# pll_schematic.net
KiCad netlist of a schematic drawn in Altium Designer
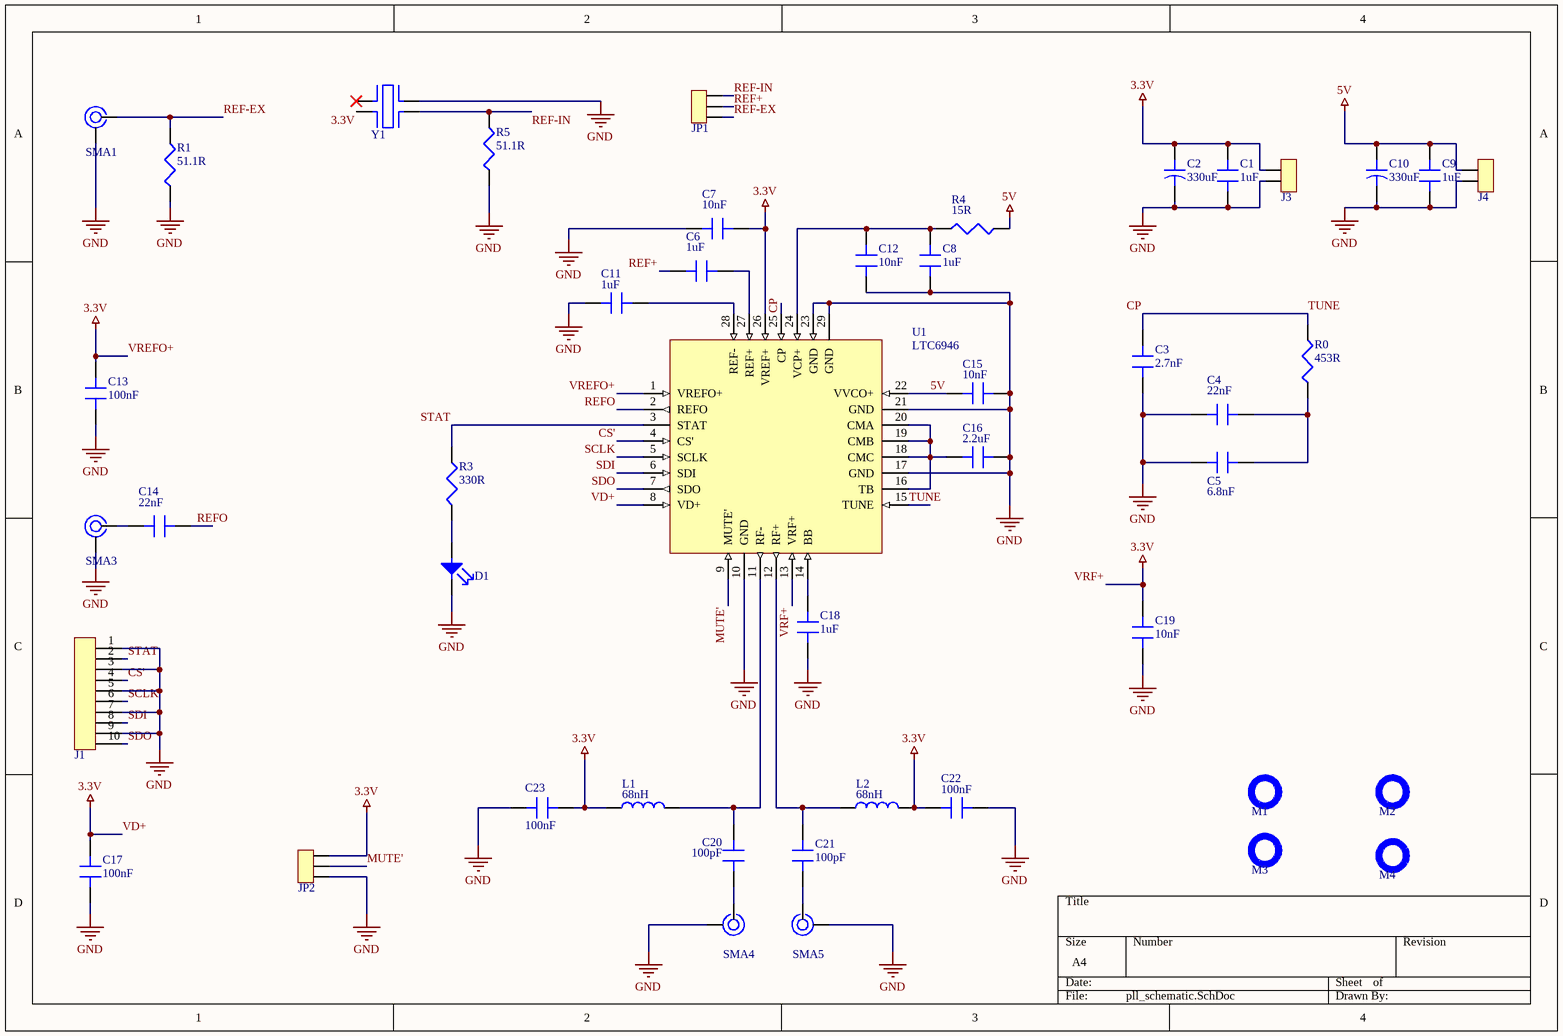
[diagram p0: pll_schematic.SchDoc]

(export (version "E")
  (design (tool "Eeschema 10.0.6"))
  (components
    (comp (ref "C1") (value "1uF") (footprint "C0603") (libsource (lib "pll_schematic_lib") (part "C")))
    (comp (ref "C2") (value "330uF") (footprint "C_TANT_D") (libsource (lib "pll_schematic_lib") (part "CP")))
    (comp (ref "C3") (value "2.7nF") (footprint "C0603") (libsource (lib "pll_schematic_lib") (part "C")))
    (comp (ref "C4") (value "22nF") (footprint "C0603") (libsource (lib "pll_schematic_lib") (part "C")))
    (comp (ref "C5") (value "6.8nF") (footprint "C0603") (libsource (lib "pll_schematic_lib") (part "C")))
    (comp (ref "C6") (value "1uF") (footprint "C0603") (libsource (lib "pll_schematic_lib") (part "C")))
    (comp (ref "C7") (value "10nF") (footprint "C0603") (libsource (lib "pll_schematic_lib") (part "C")))
    (comp (ref "C8") (value "1uF") (footprint "C0603") (libsource (lib "pll_schematic_lib") (part "C")))
    (comp (ref "C9") (value "1uF") (footprint "C0603") (libsource (lib "pll_schematic_lib") (part "C")))
    (comp (ref "C10")
      (value "330uF")
      (footprint "C_TANT_D")
      (libsource (lib "pll_schematic_lib") (part "CP"))
    )
    (comp (ref "C11") (value "1uF") (footprint "C0603") (libsource (lib "pll_schematic_lib") (part "C")))
    (comp (ref "C12") (value "10nF") (footprint "C0603") (libsource (lib "pll_schematic_lib") (part "C")))
    (comp (ref "C13") (value "100nF") (footprint "C0603") (libsource (lib "pll_schematic_lib") (part "C")))
    (comp (ref "C14") (value "22nF") (footprint "C0603") (libsource (lib "pll_schematic_lib") (part "C")))
    (comp (ref "C15") (value "10nF") (footprint "C0603") (libsource (lib "pll_schematic_lib") (part "C")))
    (comp (ref "C16") (value "2.2uF") (footprint "C0805") (libsource (lib "pll_schematic_lib") (part "C")))
    (comp (ref "C17") (value "100nF") (footprint "C0603") (libsource (lib "pll_schematic_lib") (part "C")))
    (comp (ref "C18") (value "1uF") (footprint "C0603") (libsource (lib "pll_schematic_lib") (part "C")))
    (comp (ref "C19") (value "10nF") (footprint "C0603") (libsource (lib "pll_schematic_lib") (part "C")))
    (comp (ref "C20") (value "100pF") (footprint "C0603") (libsource (lib "pll_schematic_lib") (part "C")))
    (comp (ref "C21") (value "100pF") (footprint "C0603") (libsource (lib "pll_schematic_lib") (part "C")))
    (comp (ref "C22") (value "100nF") (footprint "C0603") (libsource (lib "pll_schematic_lib") (part "C")))
    (comp (ref "C23") (value "100nF") (footprint "C0603") (libsource (lib "pll_schematic_lib") (part "C")))
    (comp (ref "D1") (value "-") (footprint "D0805") (libsource (lib "pll_schematic_lib") (part "LED")))
    (comp (ref "J1")
      (value "-")
      (footprint "IDC-2x05")
      (libsource (lib "pll_schematic_lib") (part "Conn_Gene_1x10"))
    )
    (comp (ref "J3")
      (value "-")
      (footprint "JST_XH_1X02")
      (libsource (lib "pll_schematic_lib") (part "Conn_Gene_1x02"))
    )
    (comp (ref "J4")
      (value "-")
      (footprint "JST_XH_1X02")
      (libsource (lib "pll_schematic_lib") (part "Conn_Gene_1x02"))
    )
    (comp (ref "JP1")
      (value "-")
      (footprint "PIN_HEADER_1x03")
      (libsource (lib "pll_schematic_lib") (part "Pin Header 1x03"))
    )
    (comp (ref "JP2")
      (value "-")
      (footprint "PIN_HEADER_1x03")
      (libsource (lib "pll_schematic_lib") (part "Pin Header 1x03"))
    )
    (comp (ref "L1") (value "68nH") (footprint "L0402") (libsource (lib "pll_schematic_lib") (part "L")))
    (comp (ref "L2") (value "68nH") (footprint "L0402") (libsource (lib "pll_schematic_lib") (part "L")))
    (comp (ref "M1")
      (value "MOUNTING_HOLE")
      (footprint "MOUNTING_HOLE_NP_M3")
      (description "Non-Plated")
      (libsource (lib "pll_schematic_lib") (part "MOUNTING_HOLE"))
    )
    (comp (ref "M2")
      (value "MOUNTING_HOLE")
      (footprint "MOUNTING_HOLE_NP_M3")
      (description "Non-Plated")
      (libsource (lib "pll_schematic_lib") (part "MOUNTING_HOLE"))
    )
    (comp (ref "M3")
      (value "MOUNTING_HOLE")
      (footprint "MOUNTING_HOLE_NP_M3")
      (description "Non-Plated")
      (libsource (lib "pll_schematic_lib") (part "MOUNTING_HOLE"))
    )
    (comp (ref "M4")
      (value "MOUNTING_HOLE")
      (footprint "MOUNTING_HOLE_NP_M3")
      (description "Non-Plated")
      (libsource (lib "pll_schematic_lib") (part "MOUNTING_HOLE"))
    )
    (comp (ref "R0") (value "453R") (footprint "R0603") (libsource (lib "pll_schematic_lib") (part "R")))
    (comp (ref "R1") (value "51.1R") (footprint "R0603") (libsource (lib "pll_schematic_lib") (part "R")))
    (comp (ref "R3") (value "330R") (footprint "R0603") (libsource (lib "pll_schematic_lib") (part "R")))
    (comp (ref "R4") (value "15R") (footprint "R0603") (libsource (lib "pll_schematic_lib") (part "R")))
    (comp (ref "R5") (value "51.1R") (footprint "R0603") (libsource (lib "pll_schematic_lib") (part "R")))
    (comp (ref "SMA1") (value "-") (footprint "SMA") (libsource (lib "pll_schematic_lib") (part "SMA")))
    (comp (ref "SMA3") (value "-") (footprint "SMA") (libsource (lib "pll_schematic_lib") (part "SMA")))
    (comp (ref "SMA4") (value "-") (footprint "SMA") (libsource (lib "") (part "SMA_1")))
    (comp (ref "SMA5") (value "-") (footprint "SMA") (libsource (lib "pll_schematic_lib") (part "SMA")))
    (comp (ref "U1")
      (value "LTC6946")
      (footprint "QFN50P400X500X80_HS-29N_2")
      (libsource (lib "pll_schematic_lib") (part "LTC6946IUFD-1#PBF-ND"))
    )
    (comp (ref "Y1") (value "-") (footprint "XOSC") (libsource (lib "pll_schematic_lib") (part "OSC")))
  )
  (nets
    (net (code "1") (name "/CP") (class "Default")
      (node (ref "C3") (pin "2") (pinfunction "-_2") (pintype "passive"))
      (node (ref "R0") (pin "2") (pinfunction "-_2") (pintype "passive"))
      (node (ref "U1") (pin "15") (pinfunction "TUNE_15") (pintype "input"))
      (node (ref "U1") (pin "25") (pinfunction "CP_25") (pintype "input"))
    )
    (net (code "2") (name "/CS'") (class "Default")
      (node (ref "J1") (pin "4") (pinfunction "*_4") (pintype "passive"))
      (node (ref "U1") (pin "4") (pinfunction "CS'_4") (pintype "input"))
    )
    (net (code "3") (name "/MUTE'") (class "Default")
      (node (ref "JP2") (pin "2") (pinfunction "-_2") (pintype "passive"))
      (node (ref "U1") (pin "9") (pinfunction "MUTE'_9") (pintype "input"))
    )
    (net (code "4") (name "/REF+") (class "Default")
      (node (ref "C6") (pin "1") (pinfunction "-_1") (pintype "passive"))
      (node (ref "JP1") (pin "2") (pinfunction "-_2") (pintype "passive"))
    )
    (net (code "5") (name "/REF-EX") (class "Default")
      (node (ref "JP1") (pin "3") (pinfunction "-_3") (pintype "passive"))
      (node (ref "R1") (pin "2") (pinfunction "-_2") (pintype "passive"))
      (node (ref "SMA1") (pin "1") (pinfunction "-_1") (pintype "passive"))
    )
    (net (code "6") (name "/REF-IN") (class "Default")
      (node (ref "JP1") (pin "1") (pinfunction "-_1") (pintype "passive"))
      (node (ref "R5") (pin "1") (pinfunction "-_1") (pintype "passive"))
      (node (ref "Y1") (pin "5") (pinfunction "5_5") (pintype "passive"))
    )
    (net (code "7") (name "/REFO") (class "Default")
      (node (ref "C14") (pin "2") (pinfunction "-_2") (pintype "passive"))
      (node (ref "U1") (pin "2") (pinfunction "REFO_2") (pintype "output"))
    )
    (net (code "8") (name "/SCLK") (class "Default")
      (node (ref "J1") (pin "6") (pinfunction "*_6") (pintype "passive"))
      (node (ref "U1") (pin "5") (pinfunction "SCLK_5") (pintype "input"))
    )
    (net (code "9") (name "/SDI") (class "Default")
      (node (ref "J1") (pin "8") (pinfunction "*_8") (pintype "passive"))
      (node (ref "U1") (pin "6") (pinfunction "SDI_6") (pintype "input"))
    )
    (net (code "10") (name "/SDO") (class "Default")
      (node (ref "J1") (pin "10") (pinfunction "*_10") (pintype "passive"))
      (node (ref "U1") (pin "7") (pinfunction "SDO_7") (pintype "output"))
    )
    (net (code "11") (name "/STAT") (class "Default")
      (node (ref "J1") (pin "2") (pinfunction "*_2") (pintype "passive"))
      (node (ref "R3") (pin "2") (pinfunction "-_2") (pintype "passive"))
      (node (ref "U1") (pin "3") (pinfunction "STAT_3") (pintype "passive"))
    )
    (net (code "12") (name "3.3V") (class "Default")
      (node (ref "C1") (pin "2") (pinfunction "-_2") (pintype "passive"))
      (node (ref "C13") (pin "2") (pinfunction "-_2") (pintype "passive"))
      (node (ref "C17") (pin "2") (pinfunction "-_2") (pintype "passive"))
      (node (ref "C19") (pin "2") (pinfunction "-_2") (pintype "passive"))
      (node (ref "C2") (pin "1") (pinfunction "-_1") (pintype "passive"))
      (node (ref "C22") (pin "1") (pinfunction "-_1") (pintype "passive"))
      (node (ref "C23") (pin "1") (pinfunction "-_1") (pintype "passive"))
      (node (ref "C7") (pin "1") (pinfunction "-_1") (pintype "passive"))
      (node (ref "J3") (pin "1") (pinfunction "-_1") (pintype "passive"))
      (node (ref "JP2") (pin "1") (pinfunction "-_1") (pintype "passive"))
      (node (ref "L1") (pin "1") (pinfunction "-_1") (pintype "passive"))
      (node (ref "L2") (pin "2") (pinfunction "-_2") (pintype "passive"))
      (node (ref "U1") (pin "1") (pinfunction "VREFO+_1") (pintype "input"))
      (node (ref "U1") (pin "13") (pinfunction "VRF+_13") (pintype "input"))
      (node (ref "U1") (pin "26") (pinfunction "VREF+_26") (pintype "input"))
      (node (ref "U1") (pin "8") (pinfunction "VD+_8") (pintype "input"))
      (node (ref "Y1") (pin "8") (pinfunction "8_8") (pintype "passive"))
    )
    (net (code "13") (name "5V") (class "Default")
      (node (ref "C10") (pin "1") (pinfunction "-_1") (pintype "passive"))
      (node (ref "C15") (pin "1") (pinfunction "-_1") (pintype "passive"))
      (node (ref "C9") (pin "1") (pinfunction "-_1") (pintype "passive"))
      (node (ref "J4") (pin "1") (pinfunction "-_1") (pintype "passive"))
      (node (ref "R4") (pin "2") (pinfunction "-_2") (pintype "passive"))
      (node (ref "U1") (pin "22") (pinfunction "VVCO+_22") (pintype "input"))
    )
    (net (code "14") (name "GND") (class "Default")
      (node (ref "C1") (pin "1") (pinfunction "-_1") (pintype "passive"))
      (node (ref "C10") (pin "2") (pinfunction "-_2") (pintype "passive"))
      (node (ref "C11") (pin "1") (pinfunction "-_1") (pintype "passive"))
      (node (ref "C12") (pin "2") (pinfunction "-_2") (pintype "passive"))
      (node (ref "C13") (pin "1") (pinfunction "-_1") (pintype "passive"))
      (node (ref "C15") (pin "2") (pinfunction "-_2") (pintype "passive"))
      (node (ref "C16") (pin "2") (pinfunction "-_2") (pintype "passive"))
      (node (ref "C17") (pin "1") (pinfunction "-_1") (pintype "passive"))
      (node (ref "C18") (pin "1") (pinfunction "-_1") (pintype "passive"))
      (node (ref "C19") (pin "1") (pinfunction "-_1") (pintype "passive"))
      (node (ref "C2") (pin "2") (pinfunction "-_2") (pintype "passive"))
      (node (ref "C22") (pin "2") (pinfunction "-_2") (pintype "passive"))
      (node (ref "C23") (pin "2") (pinfunction "-_2") (pintype "passive"))
      (node (ref "C3") (pin "1") (pinfunction "-_1") (pintype "passive"))
      (node (ref "C4") (pin "2") (pinfunction "-_2") (pintype "passive"))
      (node (ref "C5") (pin "2") (pinfunction "-_2") (pintype "passive"))
      (node (ref "C7") (pin "2") (pinfunction "-_2") (pintype "passive"))
      (node (ref "C8") (pin "1") (pinfunction "-_1") (pintype "passive"))
      (node (ref "C9") (pin "2") (pinfunction "-_2") (pintype "passive"))
      (node (ref "D1") (pin "C") (pinfunction "C_C") (pintype "passive"))
      (node (ref "J1") (pin "1") (pinfunction "*_1") (pintype "passive"))
      (node (ref "J1") (pin "3") (pinfunction "*_3") (pintype "passive"))
      (node (ref "J1") (pin "5") (pinfunction "*_5") (pintype "passive"))
      (node (ref "J1") (pin "7") (pinfunction "*_7") (pintype "passive"))
      (node (ref "J1") (pin "9") (pinfunction "*_9") (pintype "passive"))
      (node (ref "J3") (pin "2") (pinfunction "-_2") (pintype "passive"))
      (node (ref "J4") (pin "2") (pinfunction "-_2") (pintype "passive"))
      (node (ref "JP2") (pin "3") (pinfunction "-_3") (pintype "passive"))
      (node (ref "R1") (pin "1") (pinfunction "-_1") (pintype "passive"))
      (node (ref "R5") (pin "2") (pinfunction "-_2") (pintype "passive"))
      (node (ref "SMA1") (pin "2") (pinfunction "-_2") (pintype "passive"))
      (node (ref "SMA3") (pin "2") (pinfunction "-_2") (pintype "passive"))
      (node (ref "SMA4") (pin "2") (pinfunction "-_2") (pintype "passive"))
      (node (ref "SMA5") (pin "2") (pinfunction "-_2") (pintype "passive"))
      (node (ref "U1") (pin "10") (pinfunction "GND_10") (pintype "passive"))
      (node (ref "U1") (pin "17") (pinfunction "GND_17") (pintype "passive"))
      (node (ref "U1") (pin "21") (pinfunction "GND_21") (pintype "passive"))
      (node (ref "U1") (pin "23") (pinfunction "GND_23") (pintype "input"))
      (node (ref "U1") (pin "29") (pinfunction "GND_29") (pintype "passive"))
      (node (ref "Y1") (pin "4") (pinfunction "4_4") (pintype "passive"))
    )
    (net (code "15") (name "Net-(C4---Pad1)") (class "Default")
      (node (ref "C4") (pin "1") (pinfunction "-_1") (pintype "passive"))
      (node (ref "C5") (pin "1") (pinfunction "-_1") (pintype "passive"))
      (node (ref "R0") (pin "1") (pinfunction "-_1") (pintype "passive"))
    )
    (net (code "16") (name "Net-(C14---Pad1)") (class "Default")
      (node (ref "C14") (pin "1") (pinfunction "-_1") (pintype "passive"))
      (node (ref "SMA3") (pin "1") (pinfunction "-_1") (pintype "passive"))
    )
    (net (code "17") (name "Net-(C20---Pad1)") (class "Default")
      (node (ref "C20") (pin "1") (pinfunction "-_1") (pintype "passive"))
      (node (ref "SMA4") (pin "1") (pinfunction "-_1") (pintype "passive"))
    )
    (net (code "18") (name "Net-(C21---Pad1)") (class "Default")
      (node (ref "C21") (pin "1") (pinfunction "-_1") (pintype "passive"))
      (node (ref "SMA5") (pin "1") (pinfunction "-_1") (pintype "passive"))
    )
    (net (code "19") (name "Net-(D1-PadA)") (class "Default")
      (node (ref "D1") (pin "A") (pinfunction "A_A") (pintype "passive"))
      (node (ref "R3") (pin "1") (pinfunction "-_1") (pintype "passive"))
    )
    (net (code "20") (name "Net-(U1-BB)") (class "Default")
      (node (ref "C18") (pin "2") (pinfunction "-_2") (pintype "passive"))
      (node (ref "U1") (pin "14") (pinfunction "BB_14") (pintype "input"))
    )
    (net (code "21") (name "Net-(U1-CMA)") (class "Default")
      (node (ref "C16") (pin "1") (pinfunction "-_1") (pintype "passive"))
      (node (ref "U1") (pin "16") (pinfunction "TB_16") (pintype "passive"))
      (node (ref "U1") (pin "18") (pinfunction "CMC_18") (pintype "passive"))
      (node (ref "U1") (pin "19") (pinfunction "CMB_19") (pintype "passive"))
      (node (ref "U1") (pin "20") (pinfunction "CMA_20") (pintype "passive"))
    )
    (net (code "22") (name "Net-(U1-REF+)") (class "Default")
      (node (ref "C6") (pin "2") (pinfunction "-_2") (pintype "passive"))
      (node (ref "U1") (pin "27") (pinfunction "REF+_27") (pintype "input"))
    )
    (net (code "23") (name "Net-(U1-REF-)") (class "Default")
      (node (ref "C11") (pin "2") (pinfunction "-_2") (pintype "passive"))
      (node (ref "U1") (pin "28") (pinfunction "REF-_28") (pintype "input"))
    )
    (net (code "24") (name "Net-(U1-RF+)") (class "Default")
      (node (ref "C21") (pin "2") (pinfunction "-_2") (pintype "passive"))
      (node (ref "L2") (pin "1") (pinfunction "-_1") (pintype "passive"))
      (node (ref "U1") (pin "12") (pinfunction "RF+_12") (pintype "output"))
    )
    (net (code "25") (name "Net-(U1-RF-)") (class "Default")
      (node (ref "C20") (pin "2") (pinfunction "-_2") (pintype "passive"))
      (node (ref "L1") (pin "2") (pinfunction "-_2") (pintype "passive"))
      (node (ref "U1") (pin "11") (pinfunction "RF-_11") (pintype "output"))
    )
    (net (code "26") (name "Net-(U1-VCP+)") (class "Default")
      (node (ref "C12") (pin "1") (pinfunction "-_1") (pintype "passive"))
      (node (ref "C8") (pin "2") (pinfunction "-_2") (pintype "passive"))
      (node (ref "R4") (pin "1") (pinfunction "-_1") (pintype "passive"))
      (node (ref "U1") (pin "24") (pinfunction "VCP+_24") (pintype "input"))
    )
    (net (code "27") (name "unconnected-(Y1-Pad1)") (class "Default")
      (node (ref "Y1") (pin "1") (pinfunction "1_1") (pintype "passive+no_connect"))
    )
  )
)
